# Title.net
KiCad netlist of a schematic drawn in Altium Designer
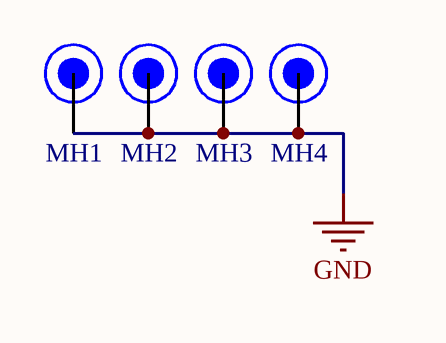
[diagram p0: Title.SchDoc]

(export (version "E")
  (design (tool "Eeschema 10.0.6"))
  (components
    (comp (ref "MH1")
      (value "Mounting Hole 6/32")
      (footprint "MH_ENG_6-32")
      (libsource (lib "SecureBot") (part "MH - 6-32"))
    )
    (comp (ref "MH2")
      (value "Mounting Hole 6/32")
      (footprint "MH_ENG_6-32")
      (libsource (lib "SecureBot") (part "MH - 6-32"))
    )
    (comp (ref "MH3")
      (value "Mounting Hole 6/32")
      (footprint "MH_ENG_6-32")
      (libsource (lib "SecureBot") (part "MH - 6-32"))
    )
    (comp (ref "MH4")
      (value "Mounting Hole 6/32")
      (footprint "MH_ENG_6-32")
      (libsource (lib "SecureBot") (part "MH - 6-32"))
    )
  )
  (nets
    (net (code "1") (name "GND") (class "Default")
      (node (ref "MH1") (pin "1") (pinfunction "1_1") (pintype "passive"))
      (node (ref "MH2") (pin "1") (pinfunction "1_1") (pintype "passive"))
      (node (ref "MH3") (pin "1") (pinfunction "1_1") (pintype "passive"))
      (node (ref "MH4") (pin "1") (pinfunction "1_1") (pintype "passive"))
    )
  )
)
